# LVDS_Receiver_CVN_CLK.net
KiCad netlist of a schematic drawn in Altium Designer
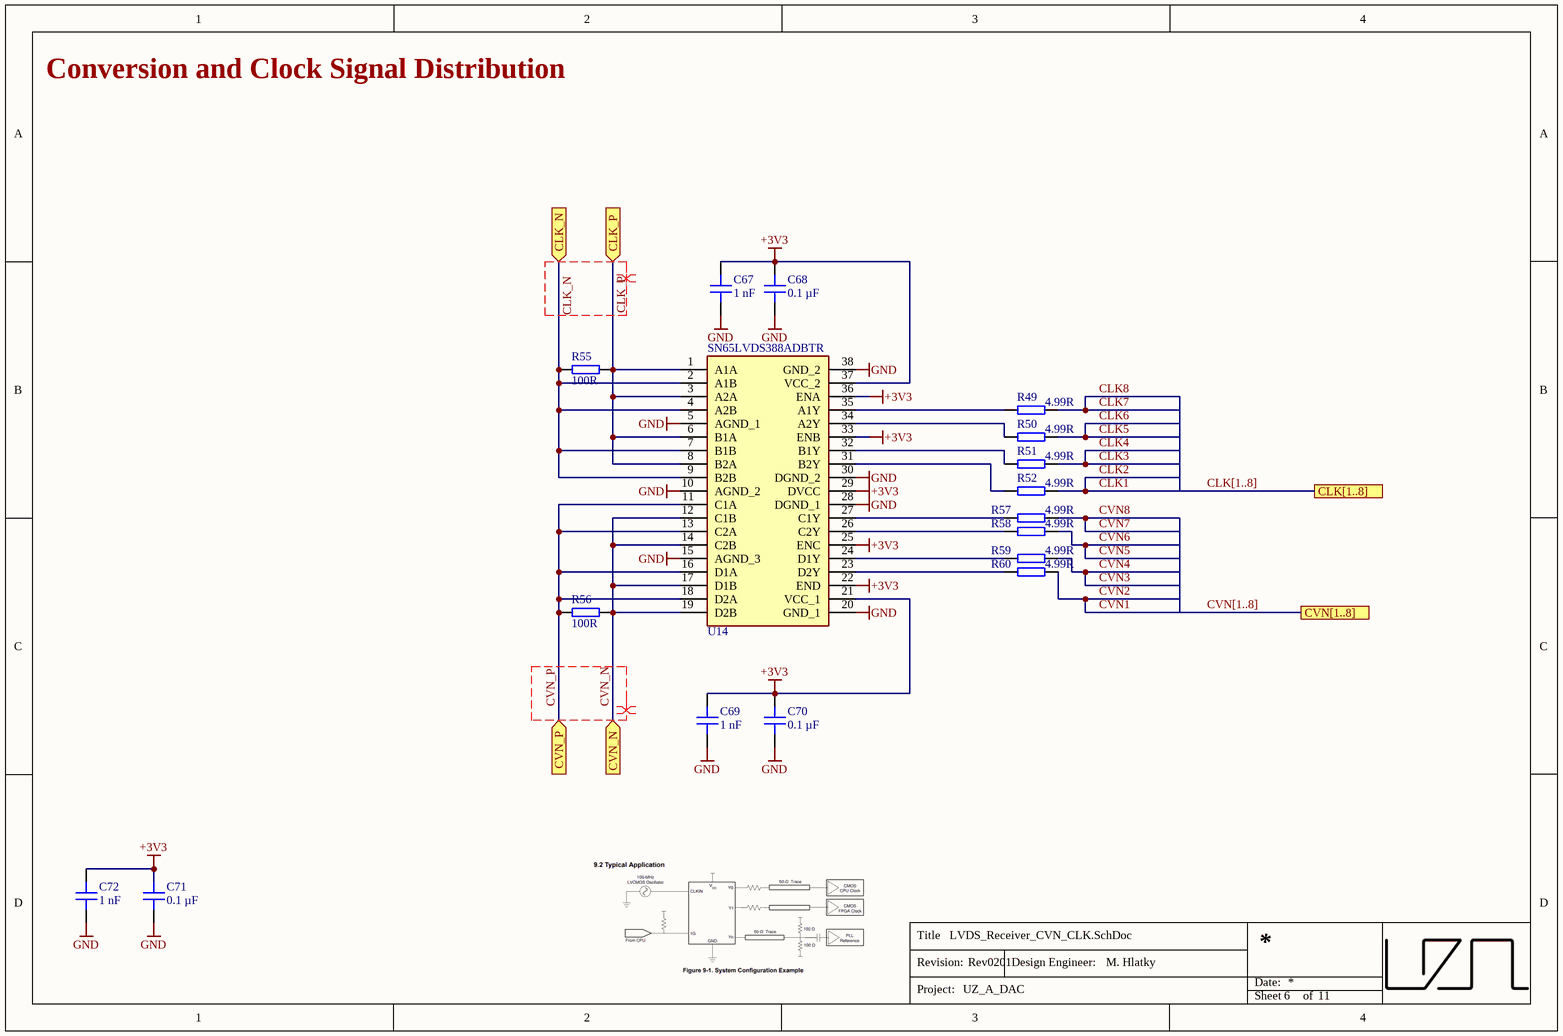
[diagram p0: LVDS_Receiver_CVN_CLK.SchDoc]

(export (version "E")
  (design (tool "Eeschema 10.0.6"))
  (components
    (comp (ref "C67")
      (value "1 nF")
      (footprint "C_1206")
      (description "Capacitor 1206, 50 VDC, 1 nF, X7R")
      (fields
        (field (name "MANUFACTURER PART NUMBER") "12065C102KAT2A")
        (field (name "MANUFACTURER") "AVX")
        (field (name "CREATED FROM") "MGremer")
      )
      (libsource (lib "user") (part "Capacitor"))
    )
    (comp (ref "C68")
      (value "0.1 µF")
      (footprint "C_0603")
      (description "Capacitor 0603, 50 VDC, 0.1 µF, X7R")
      (fields
        (field (name "MANUFACTURER PART NUMBER") "C0603X104K5RAC7411")
        (field (name "MANUFACTURER") "KEMET")
        (field (name "CREATED FROM") "MGremer")
      )
      (libsource (lib "user") (part "Capacitor"))
    )
    (comp (ref "C69")
      (value "1 nF")
      (footprint "C_1206")
      (description "Capacitor 1206, 50 VDC, 1 nF, X7R")
      (fields
        (field (name "MANUFACTURER PART NUMBER") "12065C102KAT2A")
        (field (name "MANUFACTURER") "AVX")
        (field (name "CREATED FROM") "MGremer")
      )
      (libsource (lib "user") (part "Capacitor"))
    )
    (comp (ref "C70")
      (value "0.1 µF")
      (footprint "C_0603")
      (description "Capacitor 0603, 50 VDC, 0.1 µF, X7R")
      (fields
        (field (name "MANUFACTURER PART NUMBER") "C0603X104K5RAC7411")
        (field (name "MANUFACTURER") "KEMET")
        (field (name "CREATED FROM") "MGremer")
      )
      (libsource (lib "user") (part "Capacitor"))
    )
    (comp (ref "C71")
      (value "0.1 µF")
      (footprint "C_0603")
      (description "Capacitor 0603, 50 VDC, 0.1 µF, X7R")
      (fields
        (field (name "MANUFACTURER PART NUMBER") "C0603X104K5RAC7411")
        (field (name "MANUFACTURER") "KEMET")
        (field (name "CREATED FROM") "MGremer")
      )
      (libsource (lib "user") (part "Capacitor"))
    )
    (comp (ref "C72")
      (value "1 nF")
      (footprint "C_1206")
      (description "Capacitor 1206, 50 VDC, 1 nF, X7R")
      (fields
        (field (name "MANUFACTURER PART NUMBER") "12065C102KAT2A")
        (field (name "MANUFACTURER") "AVX")
        (field (name "CREATED FROM") "MGremer")
      )
      (libsource (lib "user") (part "Capacitor"))
    )
    (comp (ref "R49")
      (value "4.99R")
      (footprint "RES 0603_1608")
      (description "SMD resistor 1%")
      (fields
        (field (name "MANUFACTURER PART NUMBER") "CRCW06034R99FKEA")
        (field (name "MANUFACTURER") "Vishay / Dale")
        (field (name "CREATED FROM") "MGremer")
      )
      (libsource (lib "user") (part "Resistor"))
    )
    (comp (ref "R50")
      (value "4.99R")
      (footprint "RES 0603_1608")
      (description "SMD resistor 1%")
      (fields
        (field (name "MANUFACTURER PART NUMBER") "CRCW06034R99FKEA")
        (field (name "MANUFACTURER") "Vishay / Dale")
        (field (name "CREATED FROM") "MGremer")
      )
      (libsource (lib "user") (part "Resistor"))
    )
    (comp (ref "R51")
      (value "4.99R")
      (footprint "RES 0603_1608")
      (description "SMD resistor 1%")
      (fields
        (field (name "MANUFACTURER PART NUMBER") "CRCW06034R99FKEA")
        (field (name "MANUFACTURER") "Vishay / Dale")
        (field (name "CREATED FROM") "MGremer")
      )
      (libsource (lib "user") (part "Resistor"))
    )
    (comp (ref "R52")
      (value "4.99R")
      (footprint "RES 0603_1608")
      (description "SMD resistor 1%")
      (fields
        (field (name "MANUFACTURER PART NUMBER") "CRCW06034R99FKEA")
        (field (name "MANUFACTURER") "Vishay / Dale")
        (field (name "CREATED FROM") "MGremer")
      )
      (libsource (lib "user") (part "Resistor"))
    )
    (comp (ref "R55")
      (value "100R")
      (footprint "RES 0603_1608")
      (description "SMD resistor 1%")
      (fields
        (field (name "MANUFACTURER PART NUMBER") "AC0603FR-13100RL")
        (field (name "MANUFACTURER") "Yageo")
        (field (name "CREATED FROM") "MGremer")
      )
      (libsource (lib "user") (part "Resistor"))
    )
    (comp (ref "R56")
      (value "100R")
      (footprint "RES 0603_1608")
      (description "SMD resistor 1%")
      (fields
        (field (name "MANUFACTURER PART NUMBER") "AC0603FR-13100RL")
        (field (name "MANUFACTURER") "Yageo")
        (field (name "CREATED FROM") "MGremer")
      )
      (libsource (lib "user") (part "Resistor"))
    )
    (comp (ref "R57")
      (value "4.99R")
      (footprint "RES 0603_1608")
      (description "SMD resistor 1%")
      (fields
        (field (name "MANUFACTURER PART NUMBER") "CRCW06034R99FKEA")
        (field (name "MANUFACTURER") "Vishay / Dale")
        (field (name "CREATED FROM") "MGremer")
      )
      (libsource (lib "user") (part "Resistor"))
    )
    (comp (ref "R58")
      (value "4.99R")
      (footprint "RES 0603_1608")
      (description "SMD resistor 1%")
      (fields
        (field (name "MANUFACTURER PART NUMBER") "CRCW06034R99FKEA")
        (field (name "MANUFACTURER") "Vishay / Dale")
        (field (name "CREATED FROM") "MGremer")
      )
      (libsource (lib "user") (part "Resistor"))
    )
    (comp (ref "R59")
      (value "4.99R")
      (footprint "RES 0603_1608")
      (description "SMD resistor 1%")
      (fields
        (field (name "MANUFACTURER PART NUMBER") "CRCW06034R99FKEA")
        (field (name "MANUFACTURER") "Vishay / Dale")
        (field (name "CREATED FROM") "MGremer")
      )
      (libsource (lib "user") (part "Resistor"))
    )
    (comp (ref "R60")
      (value "4.99R")
      (footprint "RES 0603_1608")
      (description "SMD resistor 1%")
      (fields
        (field (name "MANUFACTURER PART NUMBER") "CRCW06034R99FKEA")
        (field (name "MANUFACTURER") "Vishay / Dale")
        (field (name "CREATED FROM") "MGremer")
      )
      (libsource (lib "user") (part "Resistor"))
    )
    (comp (ref "U14")
      (value "SN65LVDS388ADBTR")
      (footprint "SOP50P640X120-38N")
      (description "High-Speed Differential Line Receivers")
      (fields (field (name "MANUFACTURER") "TI") (field (name "CREATED FROM") "MHlatky"))
      (libsource (lib "user") (part "SN65LVDS388ADBTR"))
    )
  )
  (nets
    (net (code "1") (name "+3V3") (class "Default")
      (node (ref "C67") (pin "2") (pinfunction "2_2") (pintype "passive"))
      (node (ref "C68") (pin "1") (pinfunction "1_1") (pintype "passive"))
      (node (ref "C69") (pin "2") (pinfunction "2_2") (pintype "passive"))
      (node (ref "C70") (pin "1") (pinfunction "1_1") (pintype "passive"))
      (node (ref "C71") (pin "1") (pinfunction "1_1") (pintype "passive"))
      (node (ref "C72") (pin "2") (pinfunction "2_2") (pintype "passive"))
      (node (ref "U14") (pin "21") (pinfunction "VCC_1_21") (pintype "passive"))
      (node (ref "U14") (pin "22") (pinfunction "END_22") (pintype "passive"))
      (node (ref "U14") (pin "25") (pinfunction "ENC_25") (pintype "passive"))
      (node (ref "U14") (pin "29") (pinfunction "DVCC_29") (pintype "passive"))
      (node (ref "U14") (pin "33") (pinfunction "ENB_33") (pintype "passive"))
      (node (ref "U14") (pin "36") (pinfunction "ENA_36") (pintype "passive"))
      (node (ref "U14") (pin "37") (pinfunction "VCC_2_37") (pintype "passive"))
    )
    (net (code "3") (name "/CLK2") (class "Default")
      (node (ref "R52") (pin "2") (pinfunction "2_2") (pintype "passive"))
    )
    (net (code "4") (name "/CLK4") (class "Default")
      (node (ref "R51") (pin "2") (pinfunction "2_2") (pintype "passive"))
    )
    (net (code "5") (name "/CLK6") (class "Default")
      (node (ref "R50") (pin "2") (pinfunction "2_2") (pintype "passive"))
    )
    (net (code "6") (name "/CLK8") (class "Default")
      (node (ref "R49") (pin "2") (pinfunction "2_2") (pintype "passive"))
    )
    (net (code "8") (name "/CLK_N") (class "Default")
      (node (ref "R55") (pin "1") (pinfunction "1_1") (pintype "passive"))
      (node (ref "U14") (pin "2") (pinfunction "A1B_2") (pintype "passive"))
      (node (ref "U14") (pin "4") (pinfunction "A2B_4") (pintype "passive"))
      (node (ref "U14") (pin "7") (pinfunction "B1B_7") (pintype "passive"))
      (node (ref "U14") (pin "9") (pinfunction "B2B_9") (pintype "passive"))
    )
    (net (code "9") (name "/CLK_P") (class "Default")
      (node (ref "R55") (pin "2") (pinfunction "2_2") (pintype "passive"))
      (node (ref "U14") (pin "1") (pinfunction "A1A_1") (pintype "passive"))
      (node (ref "U14") (pin "3") (pinfunction "A2A_3") (pintype "passive"))
      (node (ref "U14") (pin "6") (pinfunction "B1A_6") (pintype "passive"))
      (node (ref "U14") (pin "8") (pinfunction "B2A_8") (pintype "passive"))
    )
    (net (code "10") (name "/CVN2") (class "Default")
      (node (ref "R60") (pin "2") (pinfunction "2_2") (pintype "passive"))
    )
    (net (code "11") (name "/CVN4") (class "Default")
      (node (ref "R59") (pin "2") (pinfunction "2_2") (pintype "passive"))
    )
    (net (code "12") (name "/CVN6") (class "Default")
      (node (ref "R58") (pin "2") (pinfunction "2_2") (pintype "passive"))
    )
    (net (code "13") (name "/CVN8") (class "Default")
      (node (ref "R57") (pin "2") (pinfunction "2_2") (pintype "passive"))
    )
    (net (code "15") (name "/CVN_N") (class "Default")
      (node (ref "R56") (pin "1") (pinfunction "1_1") (pintype "passive"))
      (node (ref "U14") (pin "12") (pinfunction "C1B_12") (pintype "passive"))
      (node (ref "U14") (pin "14") (pinfunction "C2B_14") (pintype "passive"))
      (node (ref "U14") (pin "17") (pinfunction "D1B_17") (pintype "passive"))
      (node (ref "U14") (pin "19") (pinfunction "D2B_19") (pintype "passive"))
    )
    (net (code "16") (name "/CVN_P") (class "Default")
      (node (ref "R56") (pin "2") (pinfunction "2_2") (pintype "passive"))
      (node (ref "U14") (pin "11") (pinfunction "C1A_11") (pintype "passive"))
      (node (ref "U14") (pin "13") (pinfunction "C2A_13") (pintype "passive"))
      (node (ref "U14") (pin "16") (pinfunction "D1A_16") (pintype "passive"))
      (node (ref "U14") (pin "18") (pinfunction "D2A_18") (pintype "passive"))
    )
    (net (code "17") (name "GND") (class "Default")
      (node (ref "C67") (pin "1") (pinfunction "1_1") (pintype "passive"))
      (node (ref "C68") (pin "2") (pinfunction "2_2") (pintype "passive"))
      (node (ref "C69") (pin "1") (pinfunction "1_1") (pintype "passive"))
      (node (ref "C70") (pin "2") (pinfunction "2_2") (pintype "passive"))
      (node (ref "C71") (pin "2") (pinfunction "2_2") (pintype "passive"))
      (node (ref "C72") (pin "1") (pinfunction "1_1") (pintype "passive"))
      (node (ref "U14") (pin "10") (pinfunction "AGND_2_10") (pintype "passive"))
      (node (ref "U14") (pin "15") (pinfunction "AGND_3_15") (pintype "passive"))
      (node (ref "U14") (pin "20") (pinfunction "GND_1_20") (pintype "passive"))
      (node (ref "U14") (pin "28") (pinfunction "DGND_1_28") (pintype "passive"))
      (node (ref "U14") (pin "30") (pinfunction "DGND_2_30") (pintype "passive"))
      (node (ref "U14") (pin "38") (pinfunction "GND_2_38") (pintype "passive"))
      (node (ref "U14") (pin "5") (pinfunction "AGND_1_5") (pintype "passive"))
    )
    (net (code "18") (name "Net-(U14-A1Y)") (class "Default")
      (node (ref "R49") (pin "1") (pinfunction "1_1") (pintype "passive"))
      (node (ref "U14") (pin "35") (pinfunction "A1Y_35") (pintype "passive"))
    )
    (net (code "19") (name "Net-(U14-A2Y)") (class "Default")
      (node (ref "R50") (pin "1") (pinfunction "1_1") (pintype "passive"))
      (node (ref "U14") (pin "34") (pinfunction "A2Y_34") (pintype "passive"))
    )
    (net (code "20") (name "Net-(U14-B1Y)") (class "Default")
      (node (ref "R51") (pin "1") (pinfunction "1_1") (pintype "passive"))
      (node (ref "U14") (pin "32") (pinfunction "B1Y_32") (pintype "passive"))
    )
    (net (code "21") (name "Net-(U14-B2Y)") (class "Default")
      (node (ref "R52") (pin "1") (pinfunction "1_1") (pintype "passive"))
      (node (ref "U14") (pin "31") (pinfunction "B2Y_31") (pintype "passive"))
    )
    (net (code "22") (name "Net-(U14-C1Y)") (class "Default")
      (node (ref "R57") (pin "1") (pinfunction "1_1") (pintype "passive"))
      (node (ref "U14") (pin "27") (pinfunction "C1Y_27") (pintype "passive"))
    )
    (net (code "23") (name "Net-(U14-C2Y)") (class "Default")
      (node (ref "R58") (pin "1") (pinfunction "1_1") (pintype "passive"))
      (node (ref "U14") (pin "26") (pinfunction "C2Y_26") (pintype "passive"))
    )
    (net (code "24") (name "Net-(U14-D1Y)") (class "Default")
      (node (ref "R59") (pin "1") (pinfunction "1_1") (pintype "passive"))
      (node (ref "U14") (pin "24") (pinfunction "D1Y_24") (pintype "passive"))
    )
    (net (code "25") (name "Net-(U14-D2Y)") (class "Default")
      (node (ref "R60") (pin "1") (pinfunction "1_1") (pintype "passive"))
      (node (ref "U14") (pin "23") (pinfunction "D2Y_23") (pintype "passive"))
    )
  )
)
